# encoder_resolver.net
KiCad netlist of a schematic drawn in EAGLE
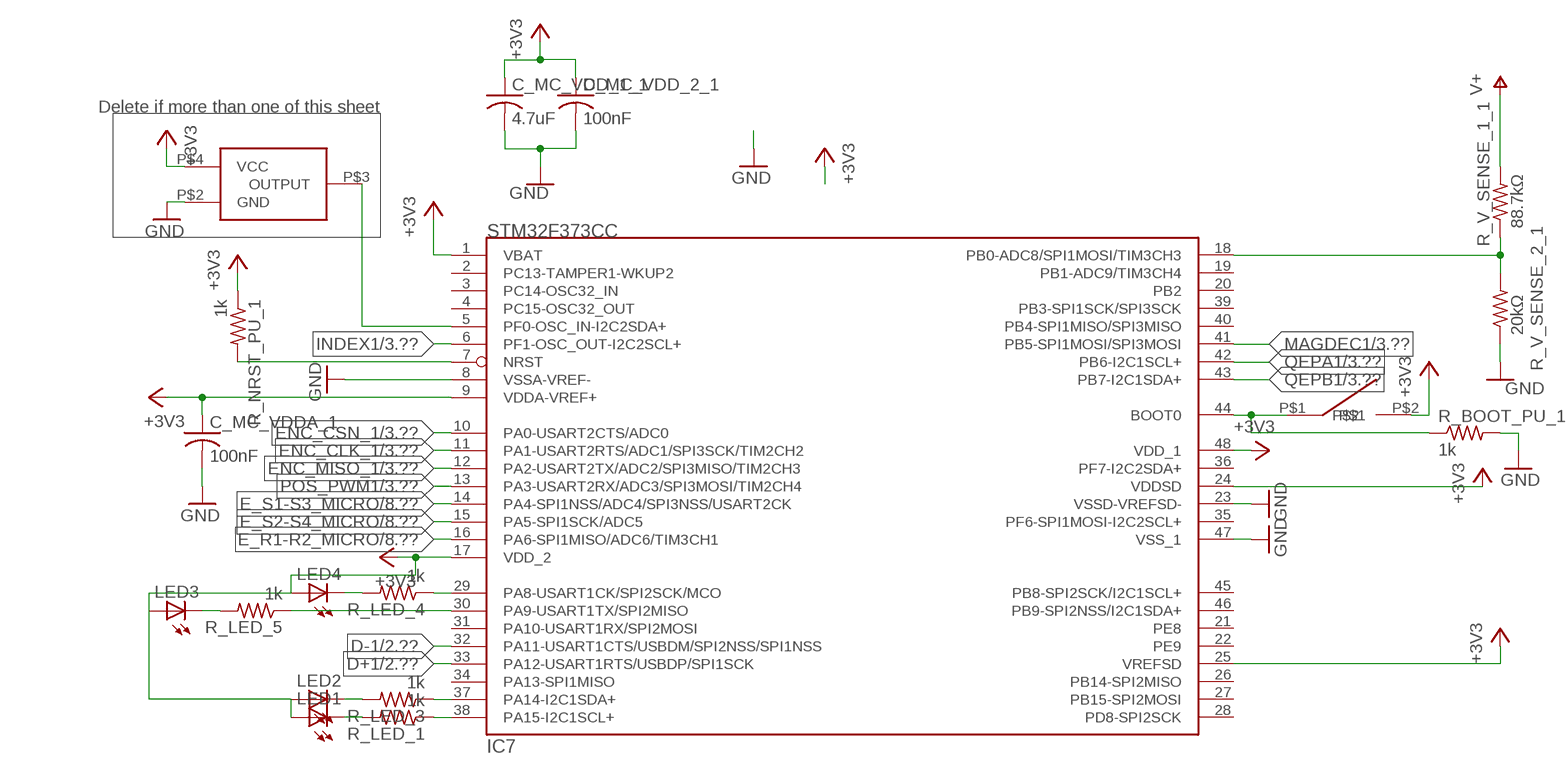
[diagram p0: schematic, sheet 1]
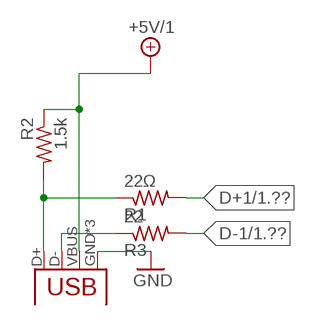
[diagram p1: schematic, sheet 2]
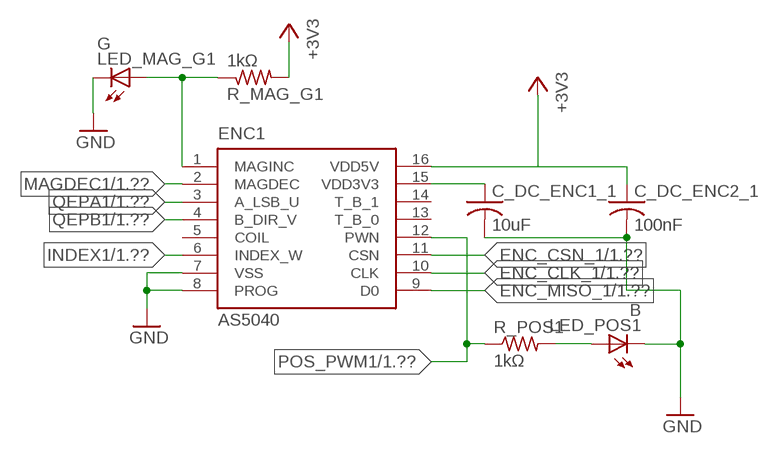
[diagram p2: schematic, sheet 3]
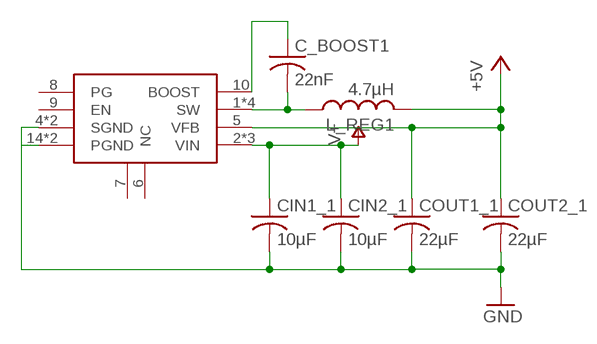
[diagram p3: schematic, sheet 4]
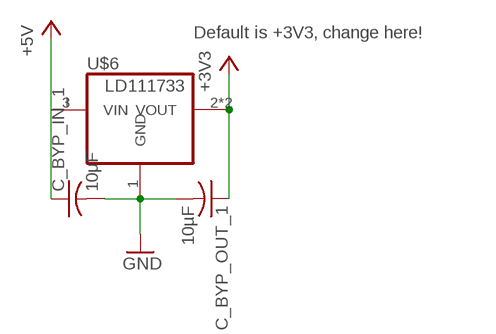
[diagram p4: schematic, sheet 5]
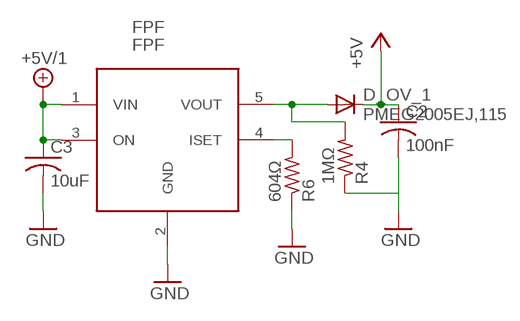
[diagram p5: schematic, sheet 6]
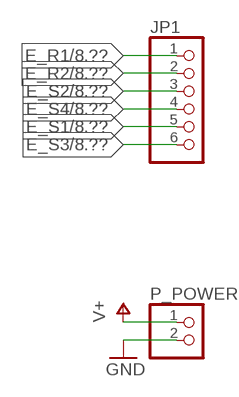
[diagram p6: schematic, sheet 7]
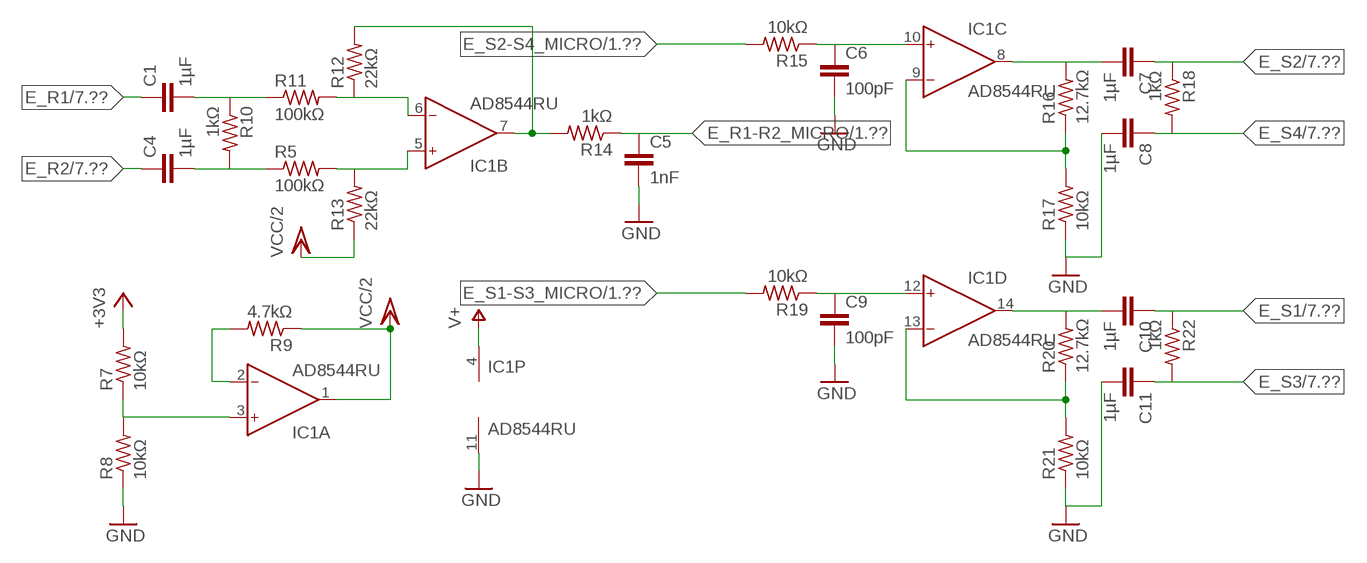
[diagram p7: schematic, sheet 8]

(export (version "E")
  (design (tool "Eeschema 10.0.6"))
  (components
    (comp (ref "R1")
      (value "22Ω")
      (footprint "eagle-import:R0603")
      (libsource (lib "eagle-import") (part "R-US_R0603"))
    )
    (comp (ref "R2")
      (value "1.5k")
      (footprint "eagle-import:R0603")
      (libsource (lib "eagle-import") (part "R-US_R0603"))
    )
    (comp (ref "R3")
      (value "22")
      (footprint "eagle-import:R0603")
      (libsource (lib "eagle-import") (part "R-US_R0603"))
    )
    (comp (ref "X1")
      (value "USB-MICROB")
      (footprint "eagle-import:USB-MICROB")
      (libsource (lib "eagle-import") (part "USB-MICROB"))
    )
    (comp (ref "JP1")
      (value "PINHD-1X6")
      (footprint "eagle-import:1X06")
      (libsource (lib "eagle-import") (part "PINHD-1X6"))
    )
    (comp (ref "P_POWER")
      (value "PINHD-1X2")
      (footprint "eagle-import:1X02")
      (libsource (lib "eagle-import") (part "PINHD-1X2"))
    )
    (comp (ref "C_MC_VDDA_1")
      (value "100nF")
      (footprint "eagle-import:C0603")
      (libsource (lib "eagle-import") (part "C-USC0603"))
    )
    (comp (ref "C_MC_VDD_1_1")
      (value "4.7uF")
      (footprint "eagle-import:C0603")
      (libsource (lib "eagle-import") (part "C-USC0603"))
    )
    (comp (ref "C_MC_VDD_2_1")
      (value "100nF")
      (footprint "eagle-import:C0603")
      (libsource (lib "eagle-import") (part "C-USC0603"))
    )
    (comp (ref "IC7")
      (value "STM32F373CC")
      (footprint "eagle-import:LQFP48")
      (libsource (lib "eagle-import") (part "STM32F373CC"))
    )
    (comp (ref "LED1")
      (value "LEDCHIPLED_0603")
      (footprint "eagle-import:CHIPLED_0603")
      (libsource (lib "eagle-import") (part "LEDCHIPLED_0603"))
    )
    (comp (ref "LED2")
      (value "LEDCHIPLED_0603")
      (footprint "eagle-import:CHIPLED_0603")
      (libsource (lib "eagle-import") (part "LEDCHIPLED_0603"))
    )
    (comp (ref "LED3")
      (value "LEDCHIPLED_0603")
      (footprint "eagle-import:CHIPLED_0603")
      (libsource (lib "eagle-import") (part "LEDCHIPLED_0603"))
    )
    (comp (ref "LED4")
      (value "LEDCHIPLED_0603")
      (footprint "eagle-import:CHIPLED_0603")
      (libsource (lib "eagle-import") (part "LEDCHIPLED_0603"))
    )
    (comp (ref "OSC1")
      (value "FOX924B")
      (footprint "eagle-import:4-SMD_5X3.2")
      (libsource (lib "eagle-import") (part "FOX924B"))
    )
    (comp (ref "R_BOOT_PU_1")
      (value "1k")
      (footprint "eagle-import:R0603")
      (libsource (lib "eagle-import") (part "R-US_R0603"))
    )
    (comp (ref "R_LED_1")
      (value "1k")
      (footprint "eagle-import:R0603")
      (libsource (lib "eagle-import") (part "R-US_R0603"))
    )
    (comp (ref "R_LED_3")
      (value "1k")
      (footprint "eagle-import:R0603")
      (libsource (lib "eagle-import") (part "R-US_R0603"))
    )
    (comp (ref "R_LED_4")
      (value "1k")
      (footprint "eagle-import:R0603")
      (libsource (lib "eagle-import") (part "R-US_R0603"))
    )
    (comp (ref "R_LED_5")
      (value "1k")
      (footprint "eagle-import:R0603")
      (libsource (lib "eagle-import") (part "R-US_R0603"))
    )
    (comp (ref "R_NRST_PU_1")
      (value "1k")
      (footprint "eagle-import:R0603")
      (libsource (lib "eagle-import") (part "R-US_R0603"))
    )
    (comp (ref "R_V_SENSE_1_1")
      (value "88.7kΩ")
      (footprint "eagle-import:R0603")
      (libsource (lib "eagle-import") (part "R-US_R0603"))
    )
    (comp (ref "R_V_SENSE_2_1")
      (value "20kΩ")
      (footprint "eagle-import:R0603")
      (libsource (lib "eagle-import") (part "R-US_R0603"))
    )
    (comp (ref "SW1")
      (value "B3U")
      (footprint "eagle-import:B3U")
      (libsource (lib "eagle-import") (part "B3U"))
    )
    (comp (ref "CIN1_1")
      (value "10µF")
      (footprint "eagle-import:C0805")
      (libsource (lib "eagle-import") (part "C-USC0805"))
    )
    (comp (ref "CIN2_1")
      (value "10µF")
      (footprint "eagle-import:C0805")
      (libsource (lib "eagle-import") (part "C-USC0805"))
    )
    (comp (ref "COUT1_1")
      (value "22µF")
      (footprint "eagle-import:C0603")
      (libsource (lib "eagle-import") (part "C-USC0603"))
    )
    (comp (ref "COUT2_1")
      (value "22µF")
      (footprint "eagle-import:C0603")
      (libsource (lib "eagle-import") (part "C-USC0603"))
    )
    (comp (ref "C_BOOST1")
      (value "22nF")
      (footprint "eagle-import:C0603")
      (libsource (lib "eagle-import") (part "C-USC0603"))
    )
    (comp (ref "L_REG1")
      (value "4.7µH")
      (footprint "eagle-import:VLC5045")
      (libsource (lib "eagle-import") (part "VLC5045"))
    )
    (comp (ref "SW_REG1")
      (value "MCP16323")
      (footprint "eagle-import:QFN16")
      (libsource (lib "eagle-import") (part "MCP16323"))
    )
    (comp (ref "C1")
      (value "1µF")
      (footprint "eagle-import:C0603")
      (libsource (lib "eagle-import") (part "C-EUC0603"))
    )
    (comp (ref "C4")
      (value "1µF")
      (footprint "eagle-import:C0603")
      (libsource (lib "eagle-import") (part "C-EUC0603"))
    )
    (comp (ref "C5")
      (value "1nF")
      (footprint "eagle-import:C0603")
      (libsource (lib "eagle-import") (part "C-EUC0603"))
    )
    (comp (ref "C6")
      (value "100pF")
      (footprint "eagle-import:C0603")
      (libsource (lib "eagle-import") (part "C-EUC0603"))
    )
    (comp (ref "C7")
      (value "1µF")
      (footprint "eagle-import:C0603")
      (libsource (lib "eagle-import") (part "C-EUC0603"))
    )
    (comp (ref "C8")
      (value "1µF")
      (footprint "eagle-import:C0603")
      (libsource (lib "eagle-import") (part "C-EUC0603"))
    )
    (comp (ref "C9")
      (value "100pF")
      (footprint "eagle-import:C0603")
      (libsource (lib "eagle-import") (part "C-EUC0603"))
    )
    (comp (ref "C10")
      (value "1µF")
      (footprint "eagle-import:C0603")
      (libsource (lib "eagle-import") (part "C-EUC0603"))
    )
    (comp (ref "C11")
      (value "1µF")
      (footprint "eagle-import:C0603")
      (libsource (lib "eagle-import") (part "C-EUC0603"))
    )
    (comp (ref "IC1")
      (value "AD8544RU")
      (footprint "eagle-import:TSSOP14")
      (fields (field (name "MPN") "AD8544ARUZ"))
      (libsource (lib "eagle-import") (part "AD8544RU"))
    )
    (comp (ref "R5")
      (value "100kΩ")
      (footprint "eagle-import:R0603")
      (libsource (lib "eagle-import") (part "R-US_R0603"))
    )
    (comp (ref "R7")
      (value "10kΩ")
      (footprint "eagle-import:R0603")
      (libsource (lib "eagle-import") (part "R-US_R0603"))
    )
    (comp (ref "R8")
      (value "10kΩ")
      (footprint "eagle-import:R0603")
      (libsource (lib "eagle-import") (part "R-US_R0603"))
    )
    (comp (ref "R9")
      (value "4.7kΩ")
      (footprint "eagle-import:R0603")
      (libsource (lib "eagle-import") (part "R-US_R0603"))
    )
    (comp (ref "R10")
      (value "1kΩ")
      (footprint "eagle-import:R0603")
      (libsource (lib "eagle-import") (part "R-US_R0603"))
    )
    (comp (ref "R11")
      (value "100kΩ")
      (footprint "eagle-import:R0603")
      (libsource (lib "eagle-import") (part "R-US_R0603"))
    )
    (comp (ref "R12")
      (value "22kΩ")
      (footprint "eagle-import:R0603")
      (libsource (lib "eagle-import") (part "R-US_R0603"))
    )
    (comp (ref "R13")
      (value "22kΩ")
      (footprint "eagle-import:R0603")
      (libsource (lib "eagle-import") (part "R-US_R0603"))
    )
    (comp (ref "R14")
      (value "1kΩ")
      (footprint "eagle-import:R0603")
      (libsource (lib "eagle-import") (part "R-US_R0603"))
    )
    (comp (ref "R15")
      (value "10kΩ")
      (footprint "eagle-import:R0603")
      (libsource (lib "eagle-import") (part "R-US_R0603"))
    )
    (comp (ref "R16")
      (value "12.7kΩ")
      (footprint "eagle-import:R0603")
      (libsource (lib "eagle-import") (part "R-US_R0603"))
    )
    (comp (ref "R17")
      (value "10kΩ")
      (footprint "eagle-import:R0603")
      (libsource (lib "eagle-import") (part "R-US_R0603"))
    )
    (comp (ref "R18")
      (value "1kΩ")
      (footprint "eagle-import:R0603")
      (libsource (lib "eagle-import") (part "R-US_R0603"))
    )
    (comp (ref "R19")
      (value "10kΩ")
      (footprint "eagle-import:R0603")
      (libsource (lib "eagle-import") (part "R-US_R0603"))
    )
    (comp (ref "R20")
      (value "12.7kΩ")
      (footprint "eagle-import:R0603")
      (libsource (lib "eagle-import") (part "R-US_R0603"))
    )
    (comp (ref "R21")
      (value "10kΩ")
      (footprint "eagle-import:R0603")
      (libsource (lib "eagle-import") (part "R-US_R0603"))
    )
    (comp (ref "R22")
      (value "1kΩ")
      (footprint "eagle-import:R0603")
      (libsource (lib "eagle-import") (part "R-US_R0603"))
    )
    (comp (ref "C_DC_ENC1_1")
      (value "10uF")
      (footprint "eagle-import:C0603")
      (libsource (lib "eagle-import") (part "C-USC0603"))
    )
    (comp (ref "C_DC_ENC2_1")
      (value "100nF")
      (footprint "eagle-import:C0603")
      (libsource (lib "eagle-import") (part "C-USC0603"))
    )
    (comp (ref "ENC1")
      (value "AS5040")
      (footprint "eagle-import:SSOP16")
      (fields (field (name "MPN") "AS5040ASSU"))
      (libsource (lib "eagle-import") (part "AS5040"))
    )
    (comp (ref "LED_MAG_G1")
      (value "G")
      (footprint "eagle-import:CHIP-LED0603")
      (libsource (lib "eagle-import") (part "LEDCHIP-LED0603"))
    )
    (comp (ref "LED_POS1")
      (value "B")
      (footprint "eagle-import:CHIP-LED0603")
      (libsource (lib "eagle-import") (part "LEDCHIP-LED0603"))
    )
    (comp (ref "R_MAG_G1")
      (value "1kΩ")
      (footprint "eagle-import:R0603")
      (libsource (lib "eagle-import") (part "R-US_R0603"))
    )
    (comp (ref "R_POS1")
      (value "1kΩ")
      (footprint "eagle-import:R0603")
      (libsource (lib "eagle-import") (part "R-US_R0603"))
    )
    (comp (ref "C2")
      (value "100nF")
      (footprint "eagle-import:C0603")
      (libsource (lib "eagle-import") (part "C-USC0603"))
    )
    (comp (ref "C3")
      (value "10uF")
      (footprint "eagle-import:C0603")
      (libsource (lib "eagle-import") (part "C-USC0603"))
    )
    (comp (ref "D_OV_1")
      (value "PMEG2005EJ,115")
      (footprint "eagle-import:SOD323-W")
      (libsource (lib "eagle-import") (part "DIODE-SOD323-W"))
    )
    (comp (ref "FPF")
      (value "FPF")
      (footprint "eagle-import:SOT23-5L")
      (libsource (lib "eagle-import") (part "FPF2123"))
    )
    (comp (ref "R4")
      (value "1MΩ")
      (footprint "eagle-import:R0603")
      (libsource (lib "eagle-import") (part "R-US_R0603"))
    )
    (comp (ref "R6")
      (value "604Ω")
      (footprint "eagle-import:R0603")
      (libsource (lib "eagle-import") (part "R-US_R0603"))
    )
    (comp (ref "C_BYP_IN_1")
      (value "10µF")
      (footprint "eagle-import:C1206")
      (libsource (lib "eagle-import") (part "C-USC1206"))
    )
    (comp (ref "C_BYP_OUT_1")
      (value "10µF")
      (footprint "eagle-import:C0603")
      (libsource (lib "eagle-import") (part "C-USC0603"))
    )
    (comp (ref "U$6")
      (value "LD111733")
      (footprint "eagle-import:SOT-223")
      (libsource (lib "eagle-import") (part "REG_SOT223LD1117XX"))
    )
  )
  (nets
    (net (code "1") (name "+3V3") (class "Default")
      (node (ref "C_BYP_OUT_1") (pin "1") (pinfunction "1_1") (pintype "passive"))
      (node (ref "C_DC_ENC2_1") (pin "1") (pinfunction "1_1") (pintype "passive"))
      (node (ref "C_MC_VDDA_1") (pin "1") (pinfunction "1_1") (pintype "passive"))
      (node (ref "C_MC_VDD_1_1") (pin "1") (pinfunction "1_1") (pintype "passive"))
      (node (ref "C_MC_VDD_2_1") (pin "1") (pinfunction "1_1") (pintype "passive"))
      (node (ref "ENC1") (pin "16") (pinfunction "VDD5V_16") (pintype "passive"))
      (node (ref "IC7") (pin "1") (pinfunction "VBAT_1") (pintype "power_in"))
      (node (ref "IC7") (pin "17") (pinfunction "VDD_2_17") (pintype "bidirectional"))
      (node (ref "IC7") (pin "24") (pinfunction "VDDSD_24") (pintype "power_in"))
      (node (ref "IC7") (pin "25") (pinfunction "VREFSD_25") (pintype "bidirectional"))
      (node (ref "IC7") (pin "48") (pinfunction "VDD_1_48") (pintype "power_in"))
      (node (ref "IC7") (pin "9") (pinfunction "VDDA-VREF+_9") (pintype "power_in"))
      (node (ref "LED1") (pin "A") (pinfunction "A_A") (pintype "passive"))
      (node (ref "LED2") (pin "A") (pinfunction "A_A") (pintype "passive"))
      (node (ref "LED3") (pin "A") (pinfunction "A_A") (pintype "passive"))
      (node (ref "LED4") (pin "A") (pinfunction "A_A") (pintype "passive"))
      (node (ref "OSC1") (pin "P$4") (pinfunction "VCC_P$4") (pintype "bidirectional"))
      (node (ref "R7") (pin "2") (pinfunction "2_2") (pintype "passive"))
      (node (ref "R_MAG_G1") (pin "2") (pinfunction "2_2") (pintype "passive"))
      (node (ref "R_NRST_PU_1") (pin "1") (pinfunction "1_1") (pintype "passive"))
      (node (ref "SW1") (pin "P$2") (pinfunction "P$2_P$2") (pintype "bidirectional"))
      (node (ref "U$6") (pin "2") (pinfunction "VOUT_2") (pintype "output"))
      (node (ref "U$6") (pin "4") (pinfunction "VOUT_4") (pintype "output"))
    )
    (net (code "2") (name "+5V") (class "Default")
      (node (ref "C2") (pin "1") (pinfunction "1_1") (pintype "passive"))
      (node (ref "COUT1_1") (pin "1") (pinfunction "1_1") (pintype "passive"))
      (node (ref "COUT2_1") (pin "1") (pinfunction "1_1") (pintype "passive"))
      (node (ref "C_BYP_IN_1") (pin "1") (pinfunction "1_1") (pintype "passive"))
      (node (ref "D_OV_1") (pin "C") (pinfunction "C_C") (pintype "passive"))
      (node (ref "L_REG1") (pin "2") (pinfunction "2_2") (pintype "passive"))
      (node (ref "SW_REG1") (pin "5") (pinfunction "VFB_5") (pintype "bidirectional"))
      (node (ref "U$6") (pin "3") (pinfunction "VIN_3") (pintype "input"))
    )
    (net (code "3") (name "+5V{slash}1") (class "Default")
      (node (ref "C3") (pin "1") (pinfunction "1_1") (pintype "passive"))
      (node (ref "FPF") (pin "1") (pinfunction "VIN_1") (pintype "bidirectional"))
      (node (ref "FPF") (pin "3") (pinfunction "ON_3") (pintype "bidirectional"))
      (node (ref "R2") (pin "1") (pinfunction "1_1") (pintype "passive"))
      (node (ref "X1") (pin "VBUS") (pinfunction "VBUS_VBUS") (pintype "bidirectional"))
    )
    (net (code "4") (name "D+1") (class "Default")
      (node (ref "IC7") (pin "33") (pinfunction "PA12-USART1RTS/USBDP/SPI1SCK_33") (pintype "bidirectional"))
      (node (ref "R1") (pin "2") (pinfunction "2_2") (pintype "passive"))
    )
    (net (code "5") (name "D-1") (class "Default")
      (node (ref "IC7") (pin "32") (pinfunction "PA11-USART1CTS/USBDM/SPI2NSS/SPI1NSS_32") (pintype "bidirectional"))
      (node (ref "R3") (pin "2") (pinfunction "2_2") (pintype "passive"))
    )
    (net (code "6") (name "ENC_CLK_1") (class "Default")
      (node (ref "ENC1") (pin "10") (pinfunction "CLK_10") (pintype "input"))
      (node (ref "IC7") (pin "11") (pinfunction "PA1-USART2RTS/ADC1/SPI3SCK/TIM2CH2_11") (pintype "bidirectional"))
    )
    (net (code "7") (name "ENC_CSN_1") (class "Default")
      (node (ref "ENC1") (pin "11") (pinfunction "CSN_11") (pintype "input"))
      (node (ref "IC7") (pin "10") (pinfunction "PA0-USART2CTS/ADC0_10") (pintype "bidirectional"))
    )
    (net (code "8") (name "ENC_MISO_1") (class "Default")
      (node (ref "ENC1") (pin "9") (pinfunction "D0_9") (pintype "tri_state"))
      (node (ref "IC7") (pin "12") (pinfunction "PA2-USART2TX/ADC2/SPI3MISO/TIM2CH3_12") (pintype "bidirectional"))
    )
    (net (code "9") (name "E_R1") (class "Default")
      (node (ref "C1") (pin "1") (pinfunction "1_1") (pintype "passive"))
      (node (ref "JP1") (pin "1") (pinfunction "1_1") (pintype "passive"))
    )
    (net (code "10") (name "E_R1-R2_MICRO") (class "Default")
      (node (ref "C5") (pin "1") (pinfunction "1_1") (pintype "passive"))
      (node (ref "IC7") (pin "16") (pinfunction "PA6-SPI1MISO/ADC6/TIM3CH1_16") (pintype "bidirectional"))
      (node (ref "R14") (pin "1") (pinfunction "1_1") (pintype "passive"))
    )
    (net (code "11") (name "E_R2") (class "Default")
      (node (ref "C4") (pin "1") (pinfunction "1_1") (pintype "passive"))
      (node (ref "JP1") (pin "2") (pinfunction "2_2") (pintype "passive"))
    )
    (net (code "12") (name "E_S1") (class "Default")
      (node (ref "C10") (pin "1") (pinfunction "1_1") (pintype "passive"))
      (node (ref "JP1") (pin "5") (pinfunction "5_5") (pintype "passive"))
      (node (ref "R22") (pin "1") (pinfunction "1_1") (pintype "passive"))
    )
    (net (code "13") (name "E_S1-S3_MICRO") (class "Default")
      (node (ref "IC7") (pin "14") (pinfunction "PA4-SPI1NSS/ADC4/SPI3NSS/USART2CK_14") (pintype "bidirectional"))
      (node (ref "R19") (pin "2") (pinfunction "2_2") (pintype "passive"))
    )
    (net (code "14") (name "E_S2") (class "Default")
      (node (ref "C7") (pin "1") (pinfunction "1_1") (pintype "passive"))
      (node (ref "JP1") (pin "3") (pinfunction "3_3") (pintype "passive"))
      (node (ref "R18") (pin "1") (pinfunction "1_1") (pintype "passive"))
    )
    (net (code "15") (name "E_S2-S4_MICRO") (class "Default")
      (node (ref "IC7") (pin "15") (pinfunction "PA5-SPI1SCK/ADC5_15") (pintype "bidirectional"))
      (node (ref "R15") (pin "2") (pinfunction "2_2") (pintype "passive"))
    )
    (net (code "16") (name "E_S3") (class "Default")
      (node (ref "C11") (pin "1") (pinfunction "1_1") (pintype "passive"))
      (node (ref "JP1") (pin "6") (pinfunction "6_6") (pintype "passive"))
      (node (ref "R22") (pin "2") (pinfunction "2_2") (pintype "passive"))
    )
    (net (code "17") (name "E_S4") (class "Default")
      (node (ref "C8") (pin "1") (pinfunction "1_1") (pintype "passive"))
      (node (ref "JP1") (pin "4") (pinfunction "4_4") (pintype "passive"))
      (node (ref "R18") (pin "2") (pinfunction "2_2") (pintype "passive"))
    )
    (net (code "18") (name "GND") (class "Default")
      (node (ref "C11") (pin "2") (pinfunction "2_2") (pintype "passive"))
      (node (ref "C2") (pin "2") (pinfunction "2_2") (pintype "passive"))
      (node (ref "C3") (pin "2") (pinfunction "2_2") (pintype "passive"))
      (node (ref "C5") (pin "2") (pinfunction "2_2") (pintype "passive"))
      (node (ref "C6") (pin "2") (pinfunction "2_2") (pintype "passive"))
      (node (ref "C8") (pin "2") (pinfunction "2_2") (pintype "passive"))
      (node (ref "C9") (pin "2") (pinfunction "2_2") (pintype "passive"))
      (node (ref "CIN1_1") (pin "2") (pinfunction "2_2") (pintype "passive"))
      (node (ref "CIN2_1") (pin "2") (pinfunction "2_2") (pintype "passive"))
      (node (ref "COUT1_1") (pin "2") (pinfunction "2_2") (pintype "passive"))
      (node (ref "COUT2_1") (pin "2") (pinfunction "2_2") (pintype "passive"))
      (node (ref "C_BYP_IN_1") (pin "2") (pinfunction "2_2") (pintype "passive"))
      (node (ref "C_BYP_OUT_1") (pin "2") (pinfunction "2_2") (pintype "passive"))
      (node (ref "C_DC_ENC1_1") (pin "2") (pinfunction "2_2") (pintype "passive"))
      (node (ref "C_DC_ENC2_1") (pin "2") (pinfunction "2_2") (pintype "passive"))
      (node (ref "C_MC_VDDA_1") (pin "2") (pinfunction "2_2") (pintype "passive"))
      (node (ref "C_MC_VDD_1_1") (pin "2") (pinfunction "2_2") (pintype "passive"))
      (node (ref "C_MC_VDD_2_1") (pin "2") (pinfunction "2_2") (pintype "passive"))
      (node (ref "ENC1") (pin "7") (pinfunction "VSS_7") (pintype "passive"))
      (node (ref "ENC1") (pin "8") (pinfunction "PROG_8") (pintype "input"))
      (node (ref "FPF") (pin "2") (pinfunction "GND_2") (pintype "bidirectional"))
      (node (ref "IC1") (pin "11") (pinfunction "V-_11") (pintype "power_in"))
      (node (ref "IC7") (pin "23") (pinfunction "VSSD-VREFSD-_23") (pintype "power_in"))
      (node (ref "IC7") (pin "47") (pinfunction "VSS_1_47") (pintype "power_in"))
      (node (ref "IC7") (pin "8") (pinfunction "VSSA-VREF-_8") (pintype "power_in"))
      (node (ref "LED_MAG_G1") (pin "C") (pinfunction "C_C") (pintype "passive"))
      (node (ref "LED_POS1") (pin "C") (pinfunction "C_C") (pintype "passive"))
      (node (ref "OSC1") (pin "P$2") (pinfunction "GND_P$2") (pintype "bidirectional"))
      (node (ref "P_POWER") (pin "2") (pinfunction "2_2") (pintype "passive"))
      (node (ref "R17") (pin "1") (pinfunction "1_1") (pintype "passive"))
      (node (ref "R21") (pin "1") (pinfunction "1_1") (pintype "passive"))
      (node (ref "R4") (pin "1") (pinfunction "1_1") (pintype "passive"))
      (node (ref "R6") (pin "1") (pinfunction "1_1") (pintype "passive"))
      (node (ref "R8") (pin "1") (pinfunction "1_1") (pintype "passive"))
      (node (ref "R_BOOT_PU_1") (pin "2") (pinfunction "2_2") (pintype "passive"))
      (node (ref "R_V_SENSE_2_1") (pin "1") (pinfunction "1_1") (pintype "passive"))
      (node (ref "SW_REG1") (pin "14") (pinfunction "PGND_14") (pintype "bidirectional"))
      (node (ref "SW_REG1") (pin "15") (pinfunction "PGND_15") (pintype "bidirectional"))
      (node (ref "SW_REG1") (pin "4") (pinfunction "SGND_4") (pintype "bidirectional"))
      (node (ref "SW_REG1") (pin "TH") (pinfunction "SGND_TH") (pintype "bidirectional"))
      (node (ref "U$6") (pin "1") (pinfunction "GND_1") (pintype "power_in"))
      (node (ref "X1") (pin "GND") (pinfunction "GND_GND") (pintype "bidirectional"))
      (node (ref "X1") (pin "MT1") (pinfunction "GND_MT1") (pintype "bidirectional"))
      (node (ref "X1") (pin "MT2") (pinfunction "GND_MT2") (pintype "bidirectional"))
    )
    (net (code "19") (name "INDEX1") (class "Default")
      (node (ref "ENC1") (pin "6") (pinfunction "INDEX_W_6") (pintype "output"))
      (node (ref "IC7") (pin "6") (pinfunction "PF1-OSC_OUT-I2C2SCL+_6") (pintype "bidirectional"))
    )
    (net (code "20") (name "MAGDEC1") (class "Default")
      (node (ref "ENC1") (pin "2") (pinfunction "MAGDEC_2") (pintype "tri_state"))
      (node (ref "IC7") (pin "41") (pinfunction "PB5-SPI1MOSI/SPI3MOSI_41") (pintype "bidirectional"))
    )
    (net (code "21") (name "Net-(C1-Pad2)") (class "Default")
      (node (ref "C1") (pin "2") (pinfunction "2_2") (pintype "passive"))
      (node (ref "R10") (pin "1") (pinfunction "1_1") (pintype "passive"))
      (node (ref "R11") (pin "1") (pinfunction "1_1") (pintype "passive"))
    )
    (net (code "22") (name "Net-(C4-Pad2)") (class "Default")
      (node (ref "C4") (pin "2") (pinfunction "2_2") (pintype "passive"))
      (node (ref "R10") (pin "2") (pinfunction "2_2") (pintype "passive"))
      (node (ref "R5") (pin "1") (pinfunction "1_1") (pintype "passive"))
    )
    (net (code "23") (name "Net-(C_BOOST1-Pad2)") (class "Default")
      (node (ref "C_BOOST1") (pin "2") (pinfunction "2_2") (pintype "passive"))
      (node (ref "L_REG1") (pin "1") (pinfunction "1_1") (pintype "passive"))
      (node (ref "SW_REG1") (pin "1") (pinfunction "SW_1") (pintype "bidirectional"))
      (node (ref "SW_REG1") (pin "12") (pinfunction "SW_12") (pintype "bidirectional"))
      (node (ref "SW_REG1") (pin "13") (pinfunction "SW_13") (pintype "bidirectional"))
      (node (ref "SW_REG1") (pin "16") (pinfunction "SW_16") (pintype "bidirectional"))
    )
    (net (code "24") (name "Net-(ENC1-MAGINC)") (class "Default")
      (node (ref "ENC1") (pin "1") (pinfunction "MAGINC_1") (pintype "tri_state"))
      (node (ref "LED_MAG_G1") (pin "A") (pinfunction "A_A") (pintype "passive"))
      (node (ref "R_MAG_G1") (pin "1") (pinfunction "1_1") (pintype "passive"))
    )
    (net (code "25") (name "Net-(ENC1-VDD3V3)") (class "Default")
      (node (ref "C_DC_ENC1_1") (pin "1") (pinfunction "1_1") (pintype "passive"))
      (node (ref "ENC1") (pin "15") (pinfunction "VDD3V3_15") (pintype "passive"))
    )
    (net (code "26") (name "Net-(FPF-ISET)") (class "Default")
      (node (ref "FPF") (pin "4") (pinfunction "ISET_4") (pintype "bidirectional"))
      (node (ref "R6") (pin "2") (pinfunction "2_2") (pintype "passive"))
    )
    (net (code "27") (name "Net-(FPF-VOUT)") (class "Default")
      (node (ref "D_OV_1") (pin "A") (pinfunction "A_A") (pintype "passive"))
      (node (ref "FPF") (pin "5") (pinfunction "VOUT_5") (pintype "bidirectional"))
      (node (ref "R4") (pin "2") (pinfunction "2_2") (pintype "passive"))
    )
    (net (code "28") (name "Net-(IC1A-IN+)") (class "Default")
      (node (ref "IC1") (pin "3") (pinfunction "IN+_3") (pintype "input"))
      (node (ref "R7") (pin "1") (pinfunction "1_1") (pintype "passive"))
      (node (ref "R8") (pin "2") (pinfunction "2_2") (pintype "passive"))
    )
    (net (code "29") (name "Net-(IC1A-IN-)") (class "Default")
      (node (ref "IC1") (pin "2") (pinfunction "IN-_2") (pintype "input"))
      (node (ref "R9") (pin "2") (pinfunction "2_2") (pintype "passive"))
    )
    (net (code "30") (name "Net-(IC1B-IN+)") (class "Default")
      (node (ref "IC1") (pin "5") (pinfunction "IN+_5") (pintype "input"))
      (node (ref "R13") (pin "2") (pinfunction "2_2") (pintype "passive"))
      (node (ref "R5") (pin "2") (pinfunction "2_2") (pintype "passive"))
    )
    (net (code "31") (name "Net-(IC1B-IN-)") (class "Default")
      (node (ref "IC1") (pin "6") (pinfunction "IN-_6") (pintype "input"))
      (node (ref "R11") (pin "2") (pinfunction "2_2") (pintype "passive"))
      (node (ref "R12") (pin "1") (pinfunction "1_1") (pintype "passive"))
    )
    (net (code "32") (name "Net-(IC1B-OUT)") (class "Default")
      (node (ref "IC1") (pin "7") (pinfunction "OUT_7") (pintype "output"))
      (node (ref "R12") (pin "2") (pinfunction "2_2") (pintype "passive"))
      (node (ref "R14") (pin "2") (pinfunction "2_2") (pintype "passive"))
    )
    (net (code "33") (name "Net-(IC1C-IN+)") (class "Default")
      (node (ref "C6") (pin "1") (pinfunction "1_1") (pintype "passive"))
      (node (ref "IC1") (pin "10") (pinfunction "IN+_10") (pintype "input"))
      (node (ref "R15") (pin "1") (pinfunction "1_1") (pintype "passive"))
    )
    (net (code "34") (name "Net-(IC1C-IN-)") (class "Default")
      (node (ref "IC1") (pin "9") (pinfunction "IN-_9") (pintype "input"))
      (node (ref "R16") (pin "1") (pinfunction "1_1") (pintype "passive"))
      (node (ref "R17") (pin "2") (pinfunction "2_2") (pintype "passive"))
    )
    (net (code "35") (name "Net-(IC1C-OUT)") (class "Default")
      (node (ref "C7") (pin "2") (pinfunction "2_2") (pintype "passive"))
      (node (ref "IC1") (pin "8") (pinfunction "OUT_8") (pintype "output"))
      (node (ref "R16") (pin "2") (pinfunction "2_2") (pintype "passive"))
    )
    (net (code "36") (name "Net-(IC1D-IN+)") (class "Default")
      (node (ref "C9") (pin "1") (pinfunction "1_1") (pintype "passive"))
      (node (ref "IC1") (pin "12") (pinfunction "IN+_12") (pintype "input"))
      (node (ref "R19") (pin "1") (pinfunction "1_1") (pintype "passive"))
    )
    (net (code "37") (name "Net-(IC1D-IN-)") (class "Default")
      (node (ref "IC1") (pin "13") (pinfunction "IN-_13") (pintype "input"))
      (node (ref "R20") (pin "1") (pinfunction "1_1") (pintype "passive"))
      (node (ref "R21") (pin "2") (pinfunction "2_2") (pintype "passive"))
    )
    (net (code "38") (name "Net-(IC1D-OUT)") (class "Default")
      (node (ref "C10") (pin "2") (pinfunction "2_2") (pintype "passive"))
      (node (ref "IC1") (pin "14") (pinfunction "OUT_14") (pintype "output"))
      (node (ref "R20") (pin "2") (pinfunction "2_2") (pintype "passive"))
    )
    (net (code "39") (name "Net-(IC7-BOOT0)") (class "Default")
      (node (ref "IC7") (pin "44") (pinfunction "BOOT0_44") (pintype "input"))
      (node (ref "R_BOOT_PU_1") (pin "1") (pinfunction "1_1") (pintype "passive"))
      (node (ref "SW1") (pin "P$1") (pinfunction "P$1_P$1") (pintype "bidirectional"))
    )
    (net (code "40") (name "Net-(IC7-NRST)") (class "Default")
      (node (ref "IC7") (pin "7") (pinfunction "NRST_7") (pintype "bidirectional"))
      (node (ref "R_NRST_PU_1") (pin "2") (pinfunction "2_2") (pintype "passive"))
    )
    (net (code "41") (name "Net-(IC7-PA8-USART1CK{slash}SPI2SCK{slash}MCO)") (class "Default")
      (node (ref "IC7") (pin "29") (pinfunction "PA8-USART1CK/SPI2SCK/MCO_29") (pintype "bidirectional"))
      (node (ref "R_LED_4") (pin "1") (pinfunction "1_1") (pintype "passive"))
    )
    (net (code "42") (name "Net-(IC7-PA9-USART1TX{slash}SPI2MISO)") (class "Default")
      (node (ref "IC7") (pin "30") (pinfunction "PA9-USART1TX/SPI2MISO_30") (pintype "bidirectional"))
      (node (ref "R_LED_5") (pin "1") (pinfunction "1_1") (pintype "passive"))
    )
    (net (code "43") (name "Net-(IC7-PA14-I2C1SDA+)") (class "Default")
      (node (ref "IC7") (pin "37") (pinfunction "PA14-I2C1SDA+_37") (pintype "bidirectional"))
      (node (ref "R_LED_3") (pin "1") (pinfunction "1_1") (pintype "passive"))
    )
    (net (code "44") (name "Net-(IC7-PA15-I2C1SCL+)") (class "Default")
      (node (ref "IC7") (pin "38") (pinfunction "PA15-I2C1SCL+_38") (pintype "bidirectional"))
      (node (ref "R_LED_1") (pin "1") (pinfunction "1_1") (pintype "passive"))
    )
    (net (code "45") (name "Net-(IC7-PB0-ADC8{slash}SPI1MOSI{slash}TIM3CH3)") (class "Default")
      (node (ref "IC7") (pin "18") (pinfunction "PB0-ADC8/SPI1MOSI/TIM3CH3_18") (pintype "bidirectional"))
      (node (ref "R_V_SENSE_1_1") (pin "1") (pinfunction "1_1") (pintype "passive"))
      (node (ref "R_V_SENSE_2_1") (pin "2") (pinfunction "2_2") (pintype "passive"))
    )
    (net (code "46") (name "Net-(IC7-PF0-OSC_IN-I2C2SDA+)") (class "Default")
      (node (ref "IC7") (pin "5") (pinfunction "PF0-OSC_IN-I2C2SDA+_5") (pintype "bidirectional"))
      (node (ref "OSC1") (pin "P$3") (pinfunction "OUTPUT_P$3") (pintype "bidirectional"))
    )
    (net (code "47") (name "Net-(LED1-PadC)") (class "Default")
      (node (ref "LED1") (pin "C") (pinfunction "C_C") (pintype "passive"))
      (node (ref "R_LED_1") (pin "2") (pinfunction "2_2") (pintype "passive"))
    )
    (net (code "48") (name "Net-(LED2-PadC)") (class "Default")
      (node (ref "LED2") (pin "C") (pinfunction "C_C") (pintype "passive"))
      (node (ref "R_LED_3") (pin "2") (pinfunction "2_2") (pintype "passive"))
    )
    (net (code "49") (name "Net-(LED3-PadC)") (class "Default")
      (node (ref "LED3") (pin "C") (pinfunction "C_C") (pintype "passive"))
      (node (ref "R_LED_5") (pin "2") (pinfunction "2_2") (pintype "passive"))
    )
    (net (code "50") (name "Net-(LED4-PadC)") (class "Default")
      (node (ref "LED4") (pin "C") (pinfunction "C_C") (pintype "passive"))
      (node (ref "R_LED_4") (pin "2") (pinfunction "2_2") (pintype "passive"))
    )
    (net (code "51") (name "Net-(LED_POS1-PadA)") (class "Default")
      (node (ref "LED_POS1") (pin "A") (pinfunction "A_A") (pintype "passive"))
      (node (ref "R_POS1") (pin "2") (pinfunction "2_2") (pintype "passive"))
    )
    (net (code "52") (name "Net-(R1-Pad1)") (class "Default")
      (node (ref "R1") (pin "1") (pinfunction "1_1") (pintype "passive"))
      (node (ref "R2") (pin "2") (pinfunction "2_2") (pintype "passive"))
      (node (ref "X1") (pin "D+") (pinfunction "D+_D+") (pintype "bidirectional"))
    )
    (net (code "53") (name "Net-(R3-Pad1)") (class "Default")
      (node (ref "R3") (pin "1") (pinfunction "1_1") (pintype "passive"))
      (node (ref "X1") (pin "D-") (pinfunction "D-_D-") (pintype "bidirectional"))
    )
    (net (code "54") (name "Net-(SW_REG1-BOOST)") (class "Default")
      (node (ref "C_BOOST1") (pin "1") (pinfunction "1_1") (pintype "passive"))
      (node (ref "SW_REG1") (pin "10") (pinfunction "BOOST_10") (pintype "bidirectional"))
    )
    (net (code "55") (name "POS_PWM1") (class "Default")
      (node (ref "ENC1") (pin "12") (pinfunction "PWN_12") (pintype "passive"))
      (node (ref "IC7") (pin "13") (pinfunction "PA3-USART2RX/ADC3/SPI3MOSI/TIM2CH4_13") (pintype "bidirectional"))
      (node (ref "R_POS1") (pin "1") (pinfunction "1_1") (pintype "passive"))
    )
    (net (code "56") (name "QEPA1") (class "Default")
      (node (ref "ENC1") (pin "3") (pinfunction "A_LSB_U_3") (pintype "output"))
      (node (ref "IC7") (pin "42") (pinfunction "PB6-I2C1SCL+_42") (pintype "bidirectional"))
    )
    (net (code "57") (name "QEPB1") (class "Default")
      (node (ref "ENC1") (pin "4") (pinfunction "B_DIR_V_4") (pintype "output"))
      (node (ref "IC7") (pin "43") (pinfunction "PB7-I2C1SDA+_43") (pintype "bidirectional"))
    )
    (net (code "58") (name "V+") (class "Default")
      (node (ref "CIN1_1") (pin "1") (pinfunction "1_1") (pintype "passive"))
      (node (ref "CIN2_1") (pin "1") (pinfunction "1_1") (pintype "passive"))
      (node (ref "IC1") (pin "4") (pinfunction "V+_4") (pintype "power_in"))
      (node (ref "P_POWER") (pin "1") (pinfunction "1_1") (pintype "passive"))
      (node (ref "R_V_SENSE_1_1") (pin "2") (pinfunction "2_2") (pintype "passive"))
      (node (ref "SW_REG1") (pin "11") (pinfunction "VIN_11") (pintype "bidirectional"))
      (node (ref "SW_REG1") (pin "2") (pinfunction "VIN_2") (pintype "bidirectional"))
      (node (ref "SW_REG1") (pin "3") (pinfunction "VIN_3") (pintype "bidirectional"))
    )
    (net (code "59") (name "VCC{slash}2") (class "Default")
      (node (ref "IC1") (pin "1") (pinfunction "OUT_1") (pintype "output"))
      (node (ref "R13") (pin "1") (pinfunction "1_1") (pintype "passive"))
      (node (ref "R9") (pin "1") (pinfunction "1_1") (pintype "passive"))
    )
    (net (code "60") (name "unconnected-(ENC1-COIL-Pad5)") (class "Default")
      (node (ref "ENC1") (pin "5") (pinfunction "COIL_5") (pintype "no_connect"))
    )
    (net (code "61") (name "unconnected-(ENC1-T_B_0-Pad13)") (class "Default")
      (node (ref "ENC1") (pin "13") (pinfunction "T_B_0_13") (pintype "no_connect"))
    )
    (net (code "62") (name "unconnected-(ENC1-T_B_1-Pad14)") (class "Default")
      (node (ref "ENC1") (pin "14") (pinfunction "T_B_1_14") (pintype "no_connect"))
    )
    (net (code "63") (name "unconnected-(IC7-PA10-USART1RX{slash}SPI2MOSI-Pad31)") (class "Default")
      (node (ref "IC7") (pin "31") (pinfunction "PA10-USART1RX/SPI2MOSI_31") (pintype "bidirectional"))
    )
    (net (code "64") (name "unconnected-(IC7-PA13-SPI1MISO-Pad34)") (class "Default")
      (node (ref "IC7") (pin "34") (pinfunction "PA13-SPI1MISO_34") (pintype "bidirectional"))
    )
    (net (code "65") (name "unconnected-(IC7-PB1-ADC9{slash}TIM3CH4-Pad19)") (class "Default")
      (node (ref "IC7") (pin "19") (pinfunction "PB1-ADC9/TIM3CH4_19") (pintype "bidirectional"))
    )
    (net (code "66") (name "unconnected-(IC7-PB2-Pad20)") (class "Default")
      (node (ref "IC7") (pin "20") (pinfunction "PB2_20") (pintype "bidirectional"))
    )
    (net (code "67") (name "unconnected-(IC7-PB3-SPI1SCK{slash}SPI3SCK-Pad39)") (class "Default")
      (node (ref "IC7") (pin "39") (pinfunction "PB3-SPI1SCK/SPI3SCK_39") (pintype "bidirectional"))
    )
    (net (code "68") (name "unconnected-(IC7-PB4-SPI1MISO{slash}SPI3MISO-Pad40)") (class "Default")
      (node (ref "IC7") (pin "40") (pinfunction "PB4-SPI1MISO/SPI3MISO_40") (pintype "bidirectional"))
    )
    (net (code "69") (name "unconnected-(IC7-PB8-SPI2SCK{slash}I2C1SCL+-Pad45)") (class "Default")
      (node (ref "IC7") (pin "45") (pinfunction "PB8-SPI2SCK/I2C1SCL+_45") (pintype "bidirectional"))
    )
    (net (code "70") (name "unconnected-(IC7-PB9-SPI2NSS{slash}I2C1SDA+-Pad46)") (class "Default")
      (node (ref "IC7") (pin "46") (pinfunction "PB9-SPI2NSS/I2C1SDA+_46") (pintype "bidirectional"))
    )
    (net (code "71") (name "unconnected-(IC7-PB14-SPI2MISO-Pad26)") (class "Default")
      (node (ref "IC7") (pin "26") (pinfunction "PB14-SPI2MISO_26") (pintype "bidirectional"))
    )
    (net (code "72") (name "unconnected-(IC7-PB15-SPI2MOSI-Pad27)") (class "Default")
      (node (ref "IC7") (pin "27") (pinfunction "PB15-SPI2MOSI_27") (pintype "bidirectional"))
    )
    (net (code "73") (name "unconnected-(IC7-PC13-TAMPER1-WKUP2-Pad2)") (class "Default")
      (node (ref "IC7") (pin "2") (pinfunction "PC13-TAMPER1-WKUP2_2") (pintype "bidirectional"))
    )
    (net (code "74") (name "unconnected-(IC7-PC14-OSC32_IN-Pad3)") (class "Default")
      (node (ref "IC7") (pin "3") (pinfunction "PC14-OSC32_IN_3") (pintype "bidirectional"))
    )
    (net (code "75") (name "unconnected-(IC7-PC15-OSC32_OUT-Pad4)") (class "Default")
      (node (ref "IC7") (pin "4") (pinfunction "PC15-OSC32_OUT_4") (pintype "bidirectional"))
    )
    (net (code "76") (name "unconnected-(IC7-PD8-SPI2SCK-Pad28)") (class "Default")
      (node (ref "IC7") (pin "28") (pinfunction "PD8-SPI2SCK_28") (pintype "bidirectional"))
    )
    (net (code "77") (name "unconnected-(IC7-PE8-Pad21)") (class "Default")
      (node (ref "IC7") (pin "21") (pinfunction "PE8_21") (pintype "bidirectional"))
    )
    (net (code "78") (name "unconnected-(IC7-PE9-Pad22)") (class "Default")
      (node (ref "IC7") (pin "22") (pinfunction "PE9_22") (pintype "bidirectional"))
    )
    (net (code "79") (name "unconnected-(IC7-PF6-SPI1MOSI-I2C2SCL+-Pad35)") (class "Default")
      (node (ref "IC7") (pin "35") (pinfunction "PF6-SPI1MOSI-I2C2SCL+_35") (pintype "bidirectional"))
    )
    (net (code "80") (name "unconnected-(IC7-PF7-I2C2SDA+-Pad36)") (class "Default")
      (node (ref "IC7") (pin "36") (pinfunction "PF7-I2C2SDA+_36") (pintype "bidirectional"))
    )
    (net (code "81") (name "unconnected-(SW_REG1-EN-Pad9)") (class "Default")
      (node (ref "SW_REG1") (pin "9") (pinfunction "EN_9") (pintype "bidirectional"))
    )
    (net (code "82") (name "unconnected-(SW_REG1-NC-Pad6)") (class "Default")
      (node (ref "SW_REG1") (pin "6") (pinfunction "NC_6") (pintype "no_connect"))
    )
    (net (code "83") (name "unconnected-(SW_REG1-NC2-Pad7)") (class "Default")
      (node (ref "SW_REG1") (pin "7") (pinfunction "NC2_7") (pintype "no_connect"))
    )
    (net (code "84") (name "unconnected-(SW_REG1-PG-Pad8)") (class "Default")
      (node (ref "SW_REG1") (pin "8") (pinfunction "PG_8") (pintype "bidirectional"))
    )
  )
)
